# Amp1.net
KiCad netlist of a schematic drawn in Altium Designer
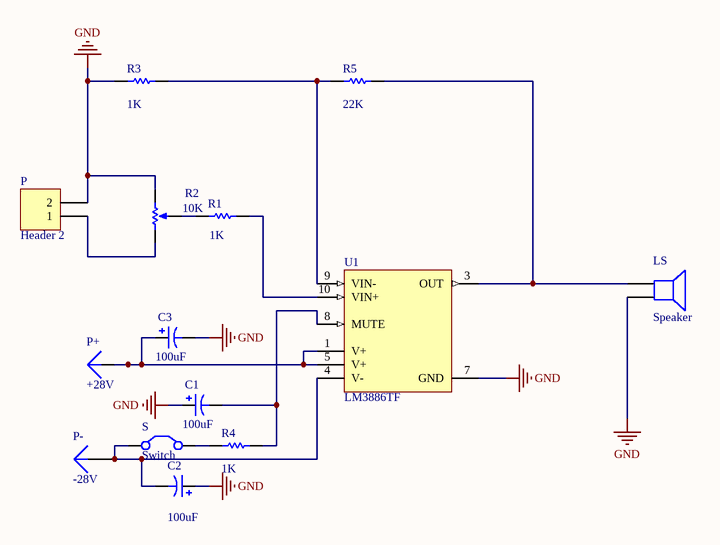
[diagram p0: Amp1.SchDoc]

(export (version "E")
  (design (tool "Eeschema 10.0.6"))
  (components
    (comp (ref "C1")
      (value "100uF")
      (footprint "RB7.6-15")
      (description "Polarized Capacitor (Radial)")
      (fields (field (name "PUBLISHER") "Altium Limited"))
      (libsource (lib "Miscellaneous Devices") (part "Cap Pol1"))
    )
    (comp (ref "C2")
      (value "100uF")
      (footprint "RB7.6-15")
      (description "Polarized Capacitor (Radial)")
      (fields (field (name "PUBLISHER") "Altium Limited"))
      (libsource (lib "Miscellaneous Devices") (part "Cap Pol1"))
    )
    (comp (ref "C3")
      (value "100uF")
      (footprint "RB7.6-15")
      (description "Polarized Capacitor (Radial)")
      (fields (field (name "PUBLISHER") "Altium Limited"))
      (libsource (lib "Miscellaneous Devices") (part "Cap Pol1"))
    )
    (comp (ref "LS")
      (value "Speaker")
      (footprint "PIN2")
      (description "Loudspeaker")
      (fields (field (name "PUBLISHER") "Altium Limited"))
      (libsource (lib "Miscellaneous Devices") (part "Speaker"))
    )
    (comp (ref "P")
      (value "Header 2")
      (footprint "HDR1X2")
      (description "Header, 2-Pin")
      (fields (field (name "PUBLISHER") "Altium Limited"))
      (libsource (lib "Miscellaneous Connectors") (part "Header 2"))
    )
    (comp (ref "P+")
      (value "+28V")
      (footprint "PIN1")
      (description "Plug")
      (fields (field (name "PUBLISHER") "Altium Limited"))
      (libsource (lib "Miscellaneous Connectors") (part "Plug"))
    )
    (comp (ref "P-")
      (value "-28V")
      (footprint "PIN1")
      (description "Plug")
      (fields (field (name "PUBLISHER") "Altium Limited"))
      (libsource (lib "Miscellaneous Connectors") (part "Plug"))
    )
    (comp (ref "R1")
      (value "1K")
      (footprint "AXIAL-0.3")
      (description "Resistor")
      (fields (field (name "PUBLISHER") "Altium Limited"))
      (libsource (lib "Miscellaneous Devices") (part "Res1"))
    )
    (comp (ref "R2")
      (value "10K")
      (footprint "VR5")
      (description "Potentiometer")
      (fields (field (name "PUBLISHER") "Altium Limited"))
      (libsource (lib "Miscellaneous Devices") (part "RPot"))
    )
    (comp (ref "R3")
      (value "1K")
      (footprint "AXIAL-0.3")
      (description "Resistor")
      (fields (field (name "PUBLISHER") "Altium Limited"))
      (libsource (lib "Miscellaneous Devices") (part "Res1"))
    )
    (comp (ref "R4")
      (value "1K")
      (footprint "AXIAL-0.3")
      (description "Resistor")
      (fields (field (name "PUBLISHER") "Altium Limited"))
      (libsource (lib "Miscellaneous Devices") (part "Res1"))
    )
    (comp (ref "R5")
      (value "22K")
      (footprint "AXIAL-0.3")
      (description "Resistor")
      (fields (field (name "PUBLISHER") "Altium Limited"))
      (libsource (lib "Miscellaneous Devices") (part "Res1"))
    )
    (comp (ref "S")
      (value "Switch")
      (footprint "RAD-0.2")
      (description "Jumper Wire")
      (fields (field (name "PUBLISHER") "Altium Limited"))
      (libsource (lib "Miscellaneous Devices") (part "Jumper"))
    )
    (comp (ref "U1")
      (value "LM3886TF")
      (footprint "TF11B")
      (description "High-Performance 68W Audio Power Amplifier with Mute, 11-pin Isolated TO220")
      (fields
        (field (name "MANUFACTURER") "National Semiconductor")
        (field (name "PUBLISHER") "Altium Limited")
      )
      (libsource (lib "NSC Audio") (part "LM3886TF"))
    )
  )
  (nets
    (net (code "1") (name "GND") (class "Default")
      (node (ref "C1") (pin "1") (pinfunction "1_1") (pintype "passive"))
      (node (ref "C2") (pin "1") (pinfunction "1_1") (pintype "passive"))
      (node (ref "C3") (pin "2") (pinfunction "2_2") (pintype "passive"))
      (node (ref "LS") (pin "2") (pinfunction "2_2") (pintype "passive"))
      (node (ref "P") (pin "2") (pinfunction "2_2") (pintype "passive"))
      (node (ref "R2") (pin "2") (pinfunction "BOT_2") (pintype "passive"))
      (node (ref "R3") (pin "1") (pinfunction "1_1") (pintype "passive"))
      (node (ref "U1") (pin "7") (pinfunction "GND_7") (pintype "power_in"))
    )
    (net (code "2") (name "Net-(C3-Pad1)") (class "Default")
      (node (ref "C3") (pin "1") (pinfunction "1_1") (pintype "passive"))
      (node (ref "P+") (pin "1") (pinfunction "1_1") (pintype "passive"))
      (node (ref "U1") (pin "1") (pinfunction "V+_1") (pintype "power_in"))
      (node (ref "U1") (pin "5") (pinfunction "V+_5") (pintype "power_in"))
    )
    (net (code "3") (name "Net-(R2-TAP)") (class "Default")
      (node (ref "R1") (pin "1") (pinfunction "1_1") (pintype "passive"))
      (node (ref "R2") (pin "3") (pinfunction "TAP_3") (pintype "passive"))
    )
    (net (code "4") (name "Net-(R2-TOP)") (class "Default")
      (node (ref "P") (pin "1") (pinfunction "1_1") (pintype "passive"))
      (node (ref "R2") (pin "1") (pinfunction "TOP_1") (pintype "passive"))
    )
    (net (code "5") (name "Net-(S-C1)") (class "Default")
      (node (ref "C2") (pin "2") (pinfunction "2_2") (pintype "passive"))
      (node (ref "P-") (pin "1") (pinfunction "1_1") (pintype "passive"))
      (node (ref "S") (pin "1") (pinfunction "C1_1") (pintype "passive"))
      (node (ref "U1") (pin "4") (pinfunction "V-_4") (pintype "power_in"))
    )
    (net (code "6") (name "Net-(S-C2)") (class "Default")
      (node (ref "R4") (pin "1") (pinfunction "1_1") (pintype "passive"))
      (node (ref "S") (pin "2") (pinfunction "C2_2") (pintype "passive"))
    )
    (net (code "7") (name "Net-(U1-MUTE)") (class "Default")
      (node (ref "C1") (pin "2") (pinfunction "2_2") (pintype "passive"))
      (node (ref "R4") (pin "2") (pinfunction "2_2") (pintype "passive"))
      (node (ref "U1") (pin "8") (pinfunction "MUTE_8") (pintype "input"))
    )
    (net (code "8") (name "Net-(U1-OUT)") (class "Default")
      (node (ref "LS") (pin "1") (pinfunction "1_1") (pintype "passive"))
      (node (ref "R5") (pin "2") (pinfunction "2_2") (pintype "passive"))
      (node (ref "U1") (pin "3") (pinfunction "OUT_3") (pintype "output"))
    )
    (net (code "9") (name "Net-(U1-VIN+)") (class "Default")
      (node (ref "R1") (pin "2") (pinfunction "2_2") (pintype "passive"))
      (node (ref "U1") (pin "10") (pinfunction "VIN+_10") (pintype "input"))
    )
    (net (code "10") (name "Net-(U1-VIN-)") (class "Default")
      (node (ref "R3") (pin "2") (pinfunction "2_2") (pintype "passive"))
      (node (ref "R5") (pin "1") (pinfunction "1_1") (pintype "passive"))
      (node (ref "U1") (pin "9") (pinfunction "VIN-_9") (pintype "input"))
    )
  )
)
